# CPU.net
KiCad netlist of a schematic drawn in Altium Designer
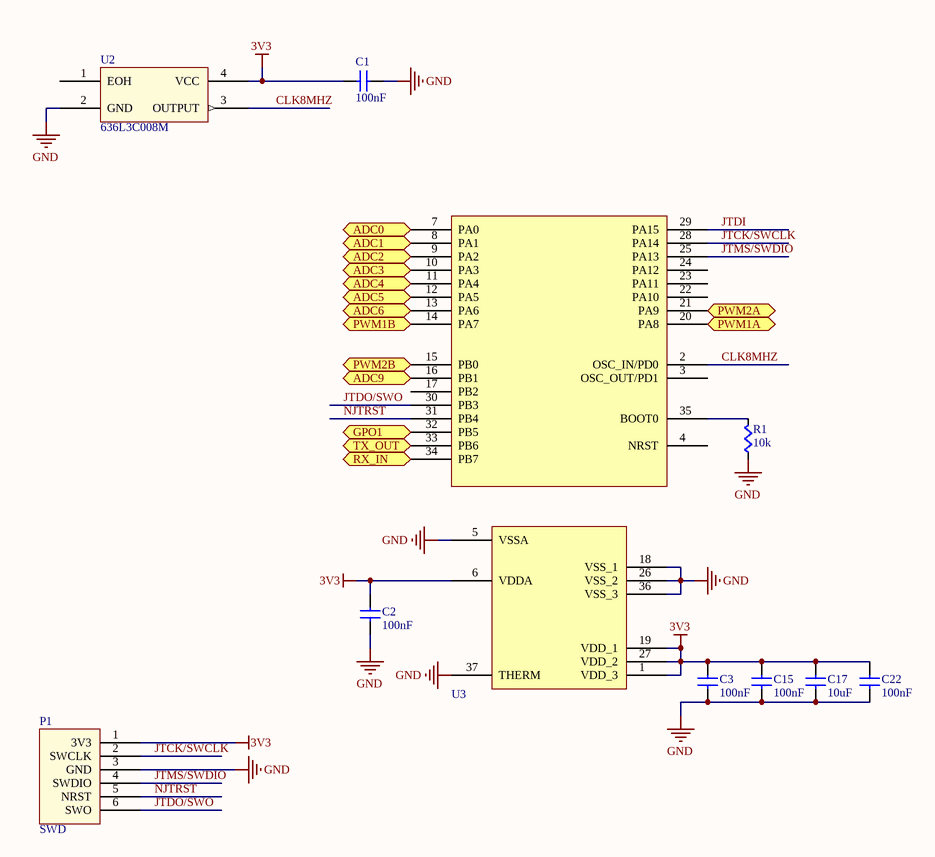
[diagram p0: CPU.SchDoc]

(export (version "E")
  (design (tool "Eeschema 10.0.6"))
  (components
    (comp (ref "C1")
      (value "100nF")
      (footprint "CAPC0603")
      (fields (field (name "Comment") "Cap"))
      (libsource (lib "Passives") (part "Cap"))
    )
    (comp (ref "C2")
      (value "100nF")
      (footprint "CAPC0603")
      (fields (field (name "Comment") "Cap"))
      (libsource (lib "Passives") (part "Cap"))
    )
    (comp (ref "C3")
      (value "100nF")
      (footprint "CAPC0603")
      (fields (field (name "Comment") "Cap"))
      (libsource (lib "Passives") (part "Cap"))
    )
    (comp (ref "C15")
      (value "100nF")
      (footprint "CAPC0603")
      (fields (field (name "Comment") "Cap"))
      (libsource (lib "Passives") (part "Cap"))
    )
    (comp (ref "C17")
      (value "10uF")
      (footprint "CAPC0603")
      (fields (field (name "Comment") "Cap"))
      (libsource (lib "Passives") (part "Cap"))
    )
    (comp (ref "C22")
      (value "100nF")
      (footprint "CAPC0603")
      (fields (field (name "Comment") "Cap"))
      (libsource (lib "Passives") (part "Cap"))
    )
    (comp (ref "P1")
      (value "SWD")
      (footprint "SWD_STM32_SMD")
      (description "SWD connector matching the pinout on STM Discovery Boards")
      (libsource (lib "Connectors") (part "SWD_STM32"))
    )
    (comp (ref "R1")
      (value "10k")
      (footprint "RES0603")
      (fields (field (name "Comment") "Res"))
      (libsource (lib "Passives") (part "Res"))
    )
    (comp (ref "U2")
      (value "636L3C008M")
      (footprint "636L3C")
      (description "HCMOS/TTL Clock Oscillator")
      (libsource (lib "ICs") (part "636L3C"))
    )
    (comp (ref "U3")
      (value "STM32F103TBU6")
      (footprint "STM32F103TBU6_NO_VIAS")
      (description "MCU ARM 32BIT 32K FLASH 36VFQFP")
      (libsource (lib "ICs") (part "STM32F103TBU6"))
    )
  )
  (nets
    (net (code "1") (name "/ADC0") (class "Default")
      (node (ref "U3") (pin "7") (pinfunction "PA0_7") (pintype "passive"))
    )
    (net (code "2") (name "/ADC1") (class "Default")
      (node (ref "U3") (pin "8") (pinfunction "PA1_8") (pintype "passive"))
    )
    (net (code "3") (name "/ADC2") (class "Default")
      (node (ref "U3") (pin "9") (pinfunction "PA2_9") (pintype "passive"))
    )
    (net (code "4") (name "/ADC3") (class "Default")
      (node (ref "U3") (pin "10") (pinfunction "PA3_10") (pintype "passive"))
    )
    (net (code "5") (name "/ADC4") (class "Default")
      (node (ref "U3") (pin "11") (pinfunction "PA4_11") (pintype "passive"))
    )
    (net (code "6") (name "/ADC5") (class "Default")
      (node (ref "U3") (pin "12") (pinfunction "PA5_12") (pintype "passive"))
    )
    (net (code "7") (name "/ADC6") (class "Default")
      (node (ref "U3") (pin "13") (pinfunction "PA6_13") (pintype "passive"))
    )
    (net (code "8") (name "/ADC9") (class "Default")
      (node (ref "U3") (pin "16") (pinfunction "PB1_16") (pintype "passive"))
    )
    (net (code "9") (name "/CLK8MHZ") (class "Default")
      (node (ref "U2") (pin "3") (pinfunction "OUTPUT_3") (pintype "output"))
      (node (ref "U3") (pin "2") (pinfunction "OSC_IN/PD0_2") (pintype "passive"))
    )
    (net (code "10") (name "/GPO1") (class "Default")
      (node (ref "U3") (pin "32") (pinfunction "PB5_32") (pintype "passive"))
    )
    (net (code "11") (name "/JTCK{slash}SWCLK") (class "Default")
      (node (ref "P1") (pin "2") (pinfunction "SWCLK_2") (pintype "passive"))
      (node (ref "U3") (pin "28") (pinfunction "PA14_28") (pintype "passive"))
    )
    (net (code "12") (name "/JTDI") (class "Default")
      (node (ref "U3") (pin "29") (pinfunction "PA15_29") (pintype "passive"))
    )
    (net (code "13") (name "/JTDO{slash}SWO") (class "Default")
      (node (ref "P1") (pin "6") (pinfunction "SWO_6") (pintype "passive"))
      (node (ref "U3") (pin "30") (pinfunction "PB3_30") (pintype "passive"))
    )
    (net (code "14") (name "/JTMS{slash}SWDIO") (class "Default")
      (node (ref "P1") (pin "4") (pinfunction "SWDIO_4") (pintype "passive"))
      (node (ref "U3") (pin "25") (pinfunction "PA13_25") (pintype "passive"))
    )
    (net (code "15") (name "/NJTRST") (class "Default")
      (node (ref "P1") (pin "5") (pinfunction "NRST_5") (pintype "passive"))
      (node (ref "U3") (pin "31") (pinfunction "PB4_31") (pintype "passive"))
    )
    (net (code "16") (name "/PWM1A") (class "Default")
      (node (ref "U3") (pin "20") (pinfunction "PA8_20") (pintype "passive"))
    )
    (net (code "17") (name "/PWM1B") (class "Default")
      (node (ref "U3") (pin "14") (pinfunction "PA7_14") (pintype "passive"))
    )
    (net (code "18") (name "/PWM2A") (class "Default")
      (node (ref "U3") (pin "21") (pinfunction "PA9_21") (pintype "passive"))
    )
    (net (code "19") (name "/PWM2B") (class "Default")
      (node (ref "U3") (pin "15") (pinfunction "PB0_15") (pintype "passive"))
    )
    (net (code "20") (name "/RX_IN") (class "Default")
      (node (ref "U3") (pin "34") (pinfunction "PB7_34") (pintype "passive"))
    )
    (net (code "21") (name "/TX_OUT") (class "Default")
      (node (ref "U3") (pin "33") (pinfunction "PB6_33") (pintype "passive"))
    )
    (net (code "22") (name "3V3") (class "Default")
      (node (ref "C1") (pin "1") (pinfunction "A_1") (pintype "passive"))
      (node (ref "C15") (pin "1") (pinfunction "A_1") (pintype "passive"))
      (node (ref "C17") (pin "1") (pinfunction "A_1") (pintype "passive"))
      (node (ref "C2") (pin "1") (pinfunction "A_1") (pintype "passive"))
      (node (ref "C22") (pin "1") (pinfunction "A_1") (pintype "passive"))
      (node (ref "C3") (pin "1") (pinfunction "A_1") (pintype "passive"))
      (node (ref "P1") (pin "1") (pinfunction "3V3_1") (pintype "passive"))
      (node (ref "U2") (pin "4") (pinfunction "VCC_4") (pintype "power_in"))
      (node (ref "U3") (pin "1") (pinfunction "VDD_3_1") (pintype "passive"))
      (node (ref "U3") (pin "19") (pinfunction "VDD_1_19") (pintype "passive"))
      (node (ref "U3") (pin "27") (pinfunction "VDD_2_27") (pintype "passive"))
      (node (ref "U3") (pin "6") (pinfunction "VDDA_6") (pintype "passive"))
    )
    (net (code "23") (name "GND") (class "Default")
      (node (ref "C1") (pin "2") (pinfunction "B_2") (pintype "passive"))
      (node (ref "C15") (pin "2") (pinfunction "B_2") (pintype "passive"))
      (node (ref "C17") (pin "2") (pinfunction "B_2") (pintype "passive"))
      (node (ref "C2") (pin "2") (pinfunction "B_2") (pintype "passive"))
      (node (ref "C22") (pin "2") (pinfunction "B_2") (pintype "passive"))
      (node (ref "C3") (pin "2") (pinfunction "B_2") (pintype "passive"))
      (node (ref "P1") (pin "3") (pinfunction "GND_3") (pintype "passive"))
      (node (ref "R1") (pin "2") (pinfunction "B_2") (pintype "passive"))
      (node (ref "U2") (pin "2") (pinfunction "GND_2") (pintype "power_in"))
      (node (ref "U3") (pin "18") (pinfunction "VSS_1_18") (pintype "passive"))
      (node (ref "U3") (pin "26") (pinfunction "VSS_2_26") (pintype "passive"))
      (node (ref "U3") (pin "36") (pinfunction "VSS_3_36") (pintype "passive"))
      (node (ref "U3") (pin "37") (pinfunction "THERM_37") (pintype "passive"))
      (node (ref "U3") (pin "5") (pinfunction "VSSA_5") (pintype "passive"))
    )
    (net (code "24") (name "Net-(R1-A)") (class "Default")
      (node (ref "R1") (pin "1") (pinfunction "A_1") (pintype "passive"))
      (node (ref "U3") (pin "35") (pinfunction "BOOT0_35") (pintype "passive"))
    )
    (net (code "25") (name "unconnected-(U2-EOH-Pad1)") (class "Default")
      (node (ref "U2") (pin "1") (pinfunction "EOH_1") (pintype "passive"))
    )
    (net (code "26") (name "unconnected-(U3-NRST-Pad4)") (class "Default")
      (node (ref "U3") (pin "4") (pinfunction "NRST_4") (pintype "passive"))
    )
    (net (code "27") (name "unconnected-(U3-OSC_OUT{slash}PD1-Pad3)") (class "Default")
      (node (ref "U3") (pin "3") (pinfunction "OSC_OUT/PD1_3") (pintype "passive"))
    )
    (net (code "28") (name "unconnected-(U3-PA10-Pad22)") (class "Default")
      (node (ref "U3") (pin "22") (pinfunction "PA10_22") (pintype "passive"))
    )
    (net (code "29") (name "unconnected-(U3-PA11-Pad23)") (class "Default")
      (node (ref "U3") (pin "23") (pinfunction "PA11_23") (pintype "passive"))
    )
    (net (code "30") (name "unconnected-(U3-PA12-Pad24)") (class "Default")
      (node (ref "U3") (pin "24") (pinfunction "PA12_24") (pintype "passive"))
    )
    (net (code "31") (name "unconnected-(U3-PB2-Pad17)") (class "Default")
      (node (ref "U3") (pin "17") (pinfunction "PB2_17") (pintype "passive"))
    )
  )
)
